# Sh_em_gost.net
KiCad netlist of a schematic drawn in Altium Designer
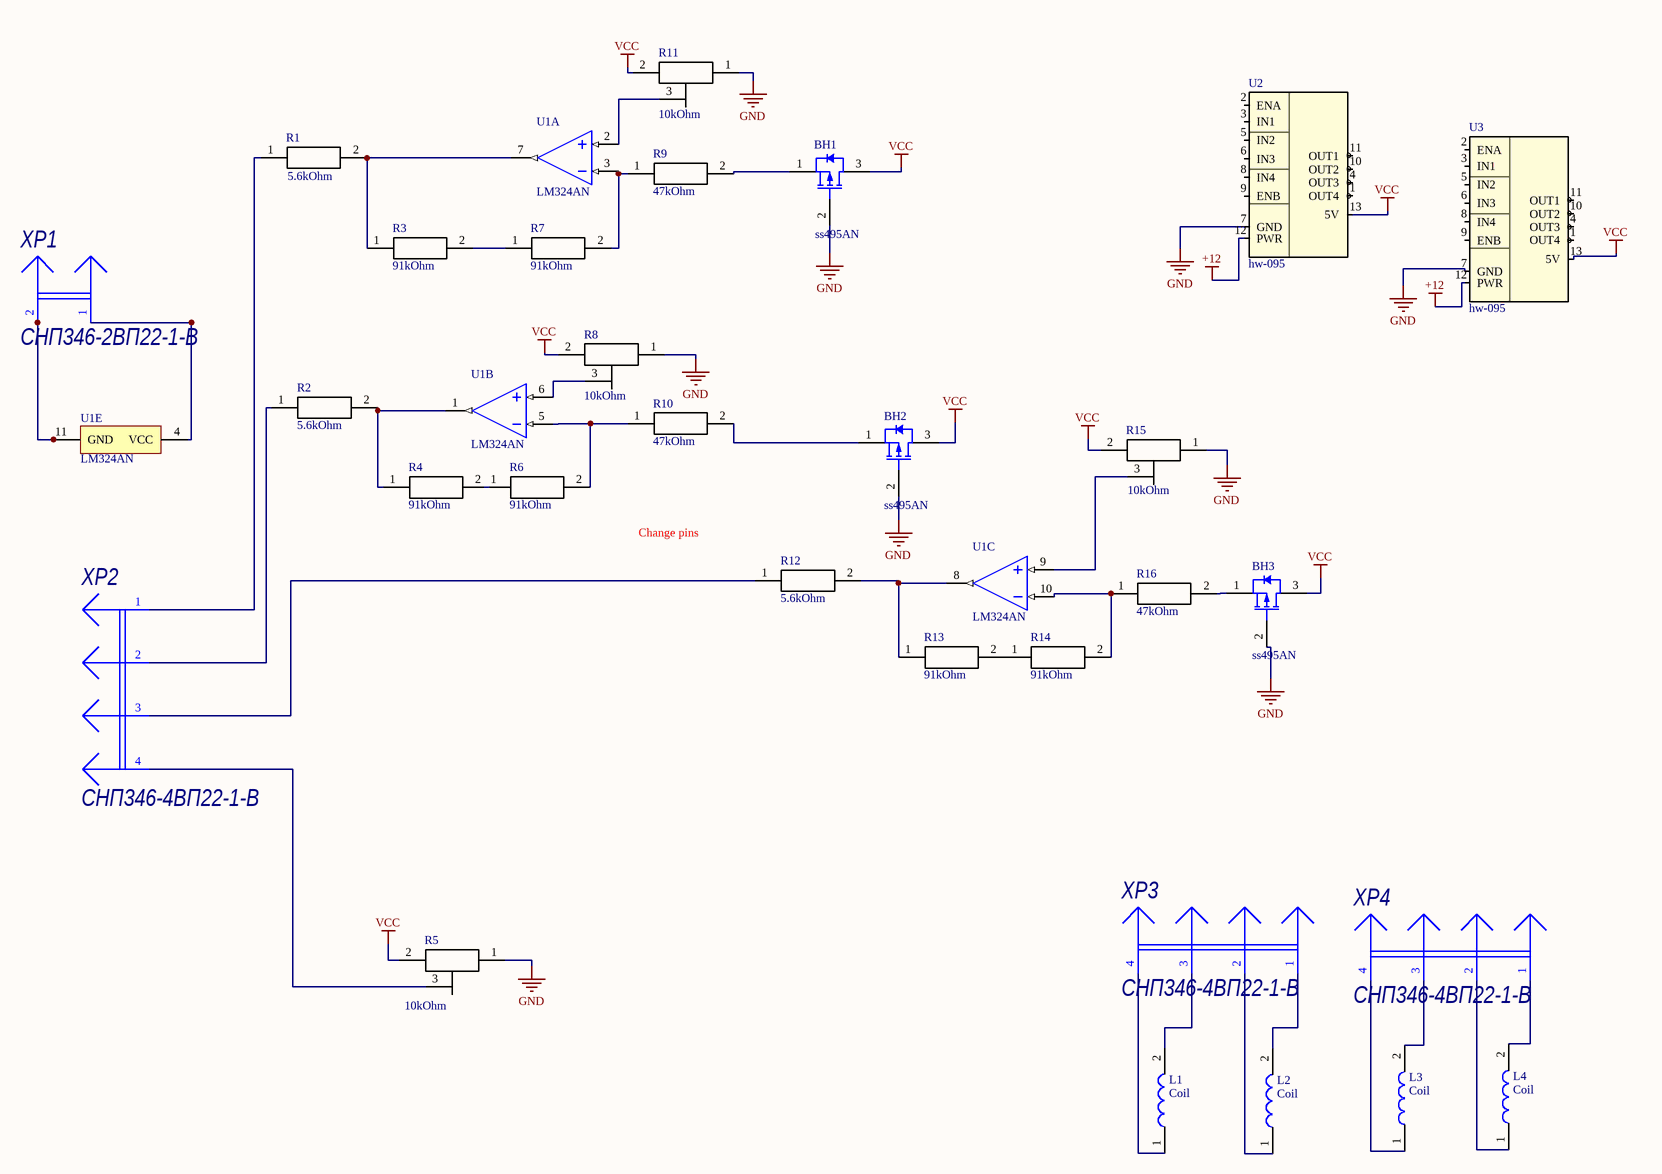
[diagram p0: Shсem gost.SchDoc]

(export (version "E")
  (design (tool "Eeschema 10.0.6"))
  (components
    (comp (ref "BH1")
      (value "ss495AN")
      (footprint "DIOD-TO92-3")
      (description "P-Channel Enhancement Mode Vertical DMOS FET, 60 VDS, 3-Pin TO92, RoHS, Bulk")
      (fields (field (name "POWER") "625mW") (field (name "MANUFACTURER") "Diodes Inc"))
      (libsource (lib "St. Petersburg State Electrotechnical University \"LETI\"") (part "PEMOS-SGD-3"))
    )
    (comp (ref "BH2")
      (value "ss495AN")
      (footprint "DIOD-TO92-3")
      (description "P-Channel Enhancement Mode Vertical DMOS FET, 60 VDS, 3-Pin TO92, RoHS, Bulk")
      (fields (field (name "POWER") "625mW") (field (name "MANUFACTURER") "Diodes Inc"))
      (libsource (lib "St. Petersburg State Electrotechnical University \"LETI\"") (part "PEMOS-SGD-3"))
    )
    (comp (ref "BH3")
      (value "ss495AN")
      (footprint "DIOD-TO92-3")
      (description "P-Channel Enhancement Mode Vertical DMOS FET, 60 VDS, 3-Pin TO92, RoHS, Bulk")
      (fields (field (name "POWER") "625mW") (field (name "MANUFACTURER") "Diodes Inc"))
      (libsource (lib "St. Petersburg State Electrotechnical University \"LETI\"") (part "PEMOS-SGD-3"))
    )
    (comp (ref "L1")
      (value "Coil")
      (footprint "INDUCTOR")
      (libsource (lib "Integrated_Library") (part "Inductor"))
    )
    (comp (ref "L2")
      (value "Coil")
      (footprint "INDUCTOR")
      (libsource (lib "Integrated_Library") (part "Inductor"))
    )
    (comp (ref "L3")
      (value "Coil")
      (footprint "INDUCTOR")
      (libsource (lib "Integrated_Library") (part "Inductor"))
    )
    (comp (ref "L4")
      (value "Coil")
      (footprint "INDUCTOR")
      (libsource (lib "Integrated_Library") (part "Inductor"))
    )
    (comp (ref "R1")
      (value "5.6kOhm")
      (footprint "RESISTOR2")
      (libsource (lib "Integrated_Library") (part "Resistor"))
    )
    (comp (ref "R2")
      (value "5.6kOhm")
      (footprint "RESISTOR2")
      (libsource (lib "Integrated_Library") (part "Resistor"))
    )
    (comp (ref "R3")
      (value "91kOhm")
      (footprint "RESISTOR2")
      (libsource (lib "Integrated_Library") (part "Resistor"))
    )
    (comp (ref "R4")
      (value "91kOhm")
      (footprint "RESISTOR2")
      (libsource (lib "Integrated_Library") (part "Resistor"))
    )
    (comp (ref "R5") (value "10kOhm") (footprint "R") (libsource (lib "Integrated_Library") (part "Res3")))
    (comp (ref "R6")
      (value "91kOhm")
      (footprint "RESISTOR2")
      (libsource (lib "Integrated_Library") (part "Resistor"))
    )
    (comp (ref "R7")
      (value "91kOhm")
      (footprint "RESISTOR2")
      (libsource (lib "Integrated_Library") (part "Resistor"))
    )
    (comp (ref "R8") (value "10kOhm") (footprint "R") (libsource (lib "Integrated_Library") (part "Res3")))
    (comp (ref "R9")
      (value "47kOhm")
      (footprint "RESISTOR2")
      (libsource (lib "Integrated_Library") (part "Resistor"))
    )
    (comp (ref "R10")
      (value "47kOhm")
      (footprint "RESISTOR2")
      (libsource (lib "Integrated_Library") (part "Resistor"))
    )
    (comp (ref "R11") (value "10kOhm") (footprint "R") (libsource (lib "Integrated_Library") (part "Res3")))
    (comp (ref "R12")
      (value "5.6kOhm")
      (footprint "RESISTOR2")
      (libsource (lib "Integrated_Library") (part "Resistor"))
    )
    (comp (ref "R13")
      (value "91kOhm")
      (footprint "RESISTOR2")
      (libsource (lib "Integrated_Library") (part "Resistor"))
    )
    (comp (ref "R14")
      (value "91kOhm")
      (footprint "RESISTOR2")
      (libsource (lib "Integrated_Library") (part "Resistor"))
    )
    (comp (ref "R15") (value "10kOhm") (footprint "R") (libsource (lib "Integrated_Library") (part "Res3")))
    (comp (ref "R16")
      (value "47kOhm")
      (footprint "RESISTOR2")
      (libsource (lib "Integrated_Library") (part "Resistor"))
    )
    (comp (ref "U1")
      (value "LM324AN")
      (footprint "TI-N0014A")
      (description "Quadruple Operational Amplifier, 1.2 MHz, 0 to 70 degC, 14-Pin PDIP (N), Pb-Free (RoHS), Tube")
      (fields (field (name "MANUFACTURER") "Texas Instruments (TI)"))
      (libsource (lib "") (part "TI-LMX24-14_1"))
    )
    (comp (ref "U2")
      (value "hw-095")
      (footprint "HW095")
      (libsource (lib "Integrated_Library") (part "hw-095"))
    )
    (comp (ref "U3")
      (value "hw-095")
      (footprint "HW095")
      (libsource (lib "Integrated_Library") (part "hw-095"))
    )
    (comp (ref "XP1")
      (value "СНП346-2ВП22-1-В")
      (footprint "PLS-2")
      (fields (field (name "MANUFACTURER") "ОАО \"Карачевский Завод \"Электродеталь\""))
      (libsource (lib "St. Petersburg State Electrotechnical University \"LETI\"") (part "Con-2-M"))
    )
    (comp (ref "XP2")
      (value "СНП346-4ВП22-1-В")
      (footprint "PLS-4")
      (fields (field (name "MANUFACTURER") "ОАО \"Карачевский Завод \"Электродеталь\""))
      (libsource (lib "St. Petersburg State Electrotechnical University \"LETI\"") (part "Con-4-M"))
    )
    (comp (ref "XP3")
      (value "СНП346-4ВП22-1-В")
      (footprint "PLS-4")
      (fields (field (name "MANUFACTURER") "ОАО \"Карачевский Завод \"Электродеталь\""))
      (libsource (lib "St. Petersburg State Electrotechnical University \"LETI\"") (part "Con-4-M"))
    )
    (comp (ref "XP4")
      (value "СНП346-4ВП22-1-В")
      (footprint "PLS-4")
      (fields (field (name "MANUFACTURER") "ОАО \"Карачевский Завод \"Электродеталь\""))
      (libsource (lib "St. Petersburg State Electrotechnical University \"LETI\"") (part "Con-4-M"))
    )
  )
  (nets
    (net (code "1") (name "+12") (class "Default")
      (node (ref "U2") (pin "12") (pinfunction "PWR_12") (pintype "power_in"))
      (node (ref "U3") (pin "12") (pinfunction "PWR_12") (pintype "power_in"))
    )
    (net (code "2") (name "GND") (class "Default")
      (node (ref "BH1") (pin "2") (pinfunction "G_2") (pintype "passive"))
      (node (ref "BH2") (pin "2") (pinfunction "G_2") (pintype "passive"))
      (node (ref "BH3") (pin "2") (pinfunction "G_2") (pintype "passive"))
      (node (ref "R11") (pin "1") (pinfunction "1_1") (pintype "passive"))
      (node (ref "R15") (pin "1") (pinfunction "1_1") (pintype "passive"))
      (node (ref "R5") (pin "1") (pinfunction "1_1") (pintype "passive"))
      (node (ref "R8") (pin "1") (pinfunction "1_1") (pintype "passive"))
      (node (ref "U2") (pin "7") (pinfunction "GND_7") (pintype "passive"))
      (node (ref "U3") (pin "7") (pinfunction "GND_7") (pintype "passive"))
    )
    (net (code "3") (name "Net-(BH1-S)") (class "Default")
      (node (ref "BH1") (pin "1") (pinfunction "S_1") (pintype "passive"))
      (node (ref "R9") (pin "2") (pinfunction "2_2") (pintype "passive"))
    )
    (net (code "4") (name "Net-(BH2-S)") (class "Default")
      (node (ref "BH2") (pin "1") (pinfunction "S_1") (pintype "passive"))
      (node (ref "R10") (pin "2") (pinfunction "2_2") (pintype "passive"))
    )
    (net (code "5") (name "Net-(BH3-S)") (class "Default")
      (node (ref "BH3") (pin "1") (pinfunction "S_1") (pintype "passive"))
      (node (ref "R16") (pin "2") (pinfunction "2_2") (pintype "passive"))
    )
    (net (code "6") (name "Net-(L1-Pad1)") (class "Default")
      (node (ref "L1") (pin "1") (pinfunction "1_1") (pintype "passive"))
      (node (ref "XP3") (pin "4") (pintype "passive"))
    )
    (net (code "7") (name "Net-(L1-Pad2)") (class "Default")
      (node (ref "L1") (pin "2") (pinfunction "2_2") (pintype "passive"))
      (node (ref "XP3") (pin "3") (pintype "passive"))
    )
    (net (code "8") (name "Net-(L2-Pad1)") (class "Default")
      (node (ref "L2") (pin "1") (pinfunction "1_1") (pintype "passive"))
      (node (ref "XP3") (pin "2") (pintype "passive"))
    )
    (net (code "9") (name "Net-(L2-Pad2)") (class "Default")
      (node (ref "L2") (pin "2") (pinfunction "2_2") (pintype "passive"))
      (node (ref "XP3") (pin "1") (pintype "passive"))
    )
    (net (code "10") (name "Net-(L3-Pad1)") (class "Default")
      (node (ref "L3") (pin "1") (pinfunction "1_1") (pintype "passive"))
      (node (ref "XP4") (pin "4") (pintype "passive"))
    )
    (net (code "11") (name "Net-(L3-Pad2)") (class "Default")
      (node (ref "L3") (pin "2") (pinfunction "2_2") (pintype "passive"))
      (node (ref "XP4") (pin "3") (pintype "passive"))
    )
    (net (code "12") (name "Net-(L4-Pad1)") (class "Default")
      (node (ref "L4") (pin "1") (pinfunction "1_1") (pintype "passive"))
      (node (ref "XP4") (pin "2") (pintype "passive"))
    )
    (net (code "13") (name "Net-(L4-Pad2)") (class "Default")
      (node (ref "L4") (pin "2") (pinfunction "2_2") (pintype "passive"))
      (node (ref "XP4") (pin "1") (pintype "passive"))
    )
    (net (code "14") (name "Net-(R1-Pad1)") (class "Default")
      (node (ref "R1") (pin "1") (pinfunction "1_1") (pintype "passive"))
      (node (ref "XP2") (pin "1") (pintype "passive"))
    )
    (net (code "15") (name "Net-(R2-Pad1)") (class "Default")
      (node (ref "R2") (pin "1") (pinfunction "1_1") (pintype "passive"))
      (node (ref "XP2") (pin "2") (pintype "passive"))
    )
    (net (code "16") (name "Net-(R3-Pad2)") (class "Default")
      (node (ref "R3") (pin "2") (pinfunction "2_2") (pintype "passive"))
      (node (ref "R7") (pin "1") (pinfunction "1_1") (pintype "passive"))
    )
    (net (code "17") (name "Net-(R4-Pad2)") (class "Default")
      (node (ref "R4") (pin "2") (pinfunction "2_2") (pintype "passive"))
      (node (ref "R6") (pin "1") (pinfunction "1_1") (pintype "passive"))
    )
    (net (code "18") (name "Net-(R5-Pad3)") (class "Default")
      (node (ref "R5") (pin "3") (pinfunction "3_3") (pintype "passive"))
      (node (ref "XP2") (pin "4") (pintype "passive"))
    )
    (net (code "19") (name "Net-(R12-Pad1)") (class "Default")
      (node (ref "R12") (pin "1") (pinfunction "1_1") (pintype "passive"))
      (node (ref "XP2") (pin "3") (pintype "passive"))
    )
    (net (code "20") (name "Net-(R13-Pad2)") (class "Default")
      (node (ref "R13") (pin "2") (pinfunction "2_2") (pintype "passive"))
      (node (ref "R14") (pin "1") (pinfunction "1_1") (pintype "passive"))
    )
    (net (code "21") (name "Net-(U1A-1IN+)") (class "Default")
      (node (ref "R7") (pin "2") (pinfunction "2_2") (pintype "passive"))
      (node (ref "R9") (pin "1") (pinfunction "1_1") (pintype "passive"))
      (node (ref "U1") (pin "3") (pinfunction "1IN+_3") (pintype "input"))
    )
    (net (code "22") (name "Net-(U1A-1IN-)") (class "Default")
      (node (ref "R11") (pin "3") (pinfunction "3_3") (pintype "passive"))
      (node (ref "U1") (pin "2") (pinfunction "1IN-_2") (pintype "input"))
    )
    (net (code "23") (name "Net-(U1A-2OUT)") (class "Default")
      (node (ref "R1") (pin "2") (pinfunction "2_2") (pintype "passive"))
      (node (ref "R3") (pin "1") (pinfunction "1_1") (pintype "passive"))
      (node (ref "U1") (pin "7") (pinfunction "2OUT_7") (pintype "output"))
    )
    (net (code "24") (name "Net-(U1B-1OUT)") (class "Default")
      (node (ref "R2") (pin "2") (pinfunction "2_2") (pintype "passive"))
      (node (ref "R4") (pin "1") (pinfunction "1_1") (pintype "passive"))
      (node (ref "U1") (pin "1") (pinfunction "1OUT_1") (pintype "output"))
    )
    (net (code "25") (name "Net-(U1B-2IN+)") (class "Default")
      (node (ref "R10") (pin "1") (pinfunction "1_1") (pintype "passive"))
      (node (ref "R6") (pin "2") (pinfunction "2_2") (pintype "passive"))
      (node (ref "U1") (pin "5") (pinfunction "2IN+_5") (pintype "input"))
    )
    (net (code "26") (name "Net-(U1B-2IN-)") (class "Default")
      (node (ref "R8") (pin "3") (pinfunction "3_3") (pintype "passive"))
      (node (ref "U1") (pin "6") (pinfunction "2IN-_6") (pintype "input"))
    )
    (net (code "27") (name "Net-(U1C-3IN+)") (class "Default")
      (node (ref "R14") (pin "2") (pinfunction "2_2") (pintype "passive"))
      (node (ref "R16") (pin "1") (pinfunction "1_1") (pintype "passive"))
      (node (ref "U1") (pin "10") (pinfunction "3IN+_10") (pintype "input"))
    )
    (net (code "28") (name "Net-(U1C-3IN-)") (class "Default")
      (node (ref "R15") (pin "3") (pinfunction "3_3") (pintype "passive"))
      (node (ref "U1") (pin "9") (pinfunction "3IN-_9") (pintype "input"))
    )
    (net (code "29") (name "Net-(U1C-3OUT)") (class "Default")
      (node (ref "R12") (pin "2") (pinfunction "2_2") (pintype "passive"))
      (node (ref "R13") (pin "1") (pinfunction "1_1") (pintype "passive"))
      (node (ref "U1") (pin "8") (pinfunction "3OUT_8") (pintype "output"))
    )
    (net (code "30") (name "Net-(U1E-GND)") (class "Default")
      (node (ref "U1") (pin "11") (pinfunction "GND_11") (pintype "power_in"))
      (node (ref "XP1") (pin "2") (pintype "passive"))
    )
    (net (code "31") (name "Net-(U1E-VCC)") (class "Default")
      (node (ref "U1") (pin "4") (pinfunction "VCC_4") (pintype "power_in"))
      (node (ref "XP1") (pin "1") (pintype "passive"))
    )
    (net (code "32") (name "VCC") (class "Default")
      (node (ref "BH1") (pin "3") (pinfunction "D_3") (pintype "passive"))
      (node (ref "BH2") (pin "3") (pinfunction "D_3") (pintype "passive"))
      (node (ref "BH3") (pin "3") (pinfunction "D_3") (pintype "passive"))
      (node (ref "R11") (pin "2") (pinfunction "2_2") (pintype "passive"))
      (node (ref "R15") (pin "2") (pinfunction "2_2") (pintype "passive"))
      (node (ref "R5") (pin "2") (pinfunction "2_2") (pintype "passive"))
      (node (ref "R8") (pin "2") (pinfunction "2_2") (pintype "passive"))
      (node (ref "U2") (pin "13") (pinfunction "5V_13") (pintype "passive"))
      (node (ref "U3") (pin "13") (pinfunction "5V_13") (pintype "passive"))
    )
    (net (code "33") (name "unconnected-(U2-ENA-Pad2)") (class "Default")
      (node (ref "U2") (pin "2") (pinfunction "ENA_2") (pintype "passive"))
    )
    (net (code "34") (name "unconnected-(U2-ENB-Pad9)") (class "Default")
      (node (ref "U2") (pin "9") (pinfunction "ENB_9") (pintype "passive"))
    )
    (net (code "35") (name "unconnected-(U2-IN1-Pad3)") (class "Default")
      (node (ref "U2") (pin "3") (pinfunction "IN1_3") (pintype "passive"))
    )
    (net (code "36") (name "unconnected-(U2-IN2-Pad5)") (class "Default")
      (node (ref "U2") (pin "5") (pinfunction "IN2_5") (pintype "passive"))
    )
    (net (code "37") (name "unconnected-(U2-IN3-Pad6)") (class "Default")
      (node (ref "U2") (pin "6") (pinfunction "IN3_6") (pintype "passive"))
    )
    (net (code "38") (name "unconnected-(U2-IN4-Pad8)") (class "Default")
      (node (ref "U2") (pin "8") (pinfunction "IN4_8") (pintype "passive"))
    )
    (net (code "39") (name "unconnected-(U2-OUT1-Pad11)") (class "Default")
      (node (ref "U2") (pin "11") (pinfunction "OUT1_11") (pintype "passive"))
    )
    (net (code "40") (name "unconnected-(U2-OUT2-Pad10)") (class "Default")
      (node (ref "U2") (pin "10") (pinfunction "OUT2_10") (pintype "passive"))
    )
    (net (code "41") (name "unconnected-(U2-OUT3-Pad4)") (class "Default")
      (node (ref "U2") (pin "4") (pinfunction "OUT3_4") (pintype "passive"))
    )
    (net (code "42") (name "unconnected-(U2-OUT4-Pad1)") (class "Default")
      (node (ref "U2") (pin "1") (pinfunction "OUT4_1") (pintype "passive"))
    )
    (net (code "43") (name "unconnected-(U3-ENA-Pad2)") (class "Default")
      (node (ref "U3") (pin "2") (pinfunction "ENA_2") (pintype "passive"))
    )
    (net (code "44") (name "unconnected-(U3-ENB-Pad9)") (class "Default")
      (node (ref "U3") (pin "9") (pinfunction "ENB_9") (pintype "passive"))
    )
    (net (code "45") (name "unconnected-(U3-IN1-Pad3)") (class "Default")
      (node (ref "U3") (pin "3") (pinfunction "IN1_3") (pintype "passive"))
    )
    (net (code "46") (name "unconnected-(U3-IN2-Pad5)") (class "Default")
      (node (ref "U3") (pin "5") (pinfunction "IN2_5") (pintype "passive"))
    )
    (net (code "47") (name "unconnected-(U3-IN3-Pad6)") (class "Default")
      (node (ref "U3") (pin "6") (pinfunction "IN3_6") (pintype "passive"))
    )
    (net (code "48") (name "unconnected-(U3-IN4-Pad8)") (class "Default")
      (node (ref "U3") (pin "8") (pinfunction "IN4_8") (pintype "passive"))
    )
    (net (code "49") (name "unconnected-(U3-OUT1-Pad11)") (class "Default")
      (node (ref "U3") (pin "11") (pinfunction "OUT1_11") (pintype "passive"))
    )
    (net (code "50") (name "unconnected-(U3-OUT2-Pad10)") (class "Default")
      (node (ref "U3") (pin "10") (pinfunction "OUT2_10") (pintype "passive"))
    )
    (net (code "51") (name "unconnected-(U3-OUT3-Pad4)") (class "Default")
      (node (ref "U3") (pin "4") (pinfunction "OUT3_4") (pintype "passive"))
    )
    (net (code "52") (name "unconnected-(U3-OUT4-Pad1)") (class "Default")
      (node (ref "U3") (pin "1") (pinfunction "OUT4_1") (pintype "passive"))
    )
  )
)
